# bare-bones-arduino.net
KiCad netlist of a schematic drawn in EAGLE
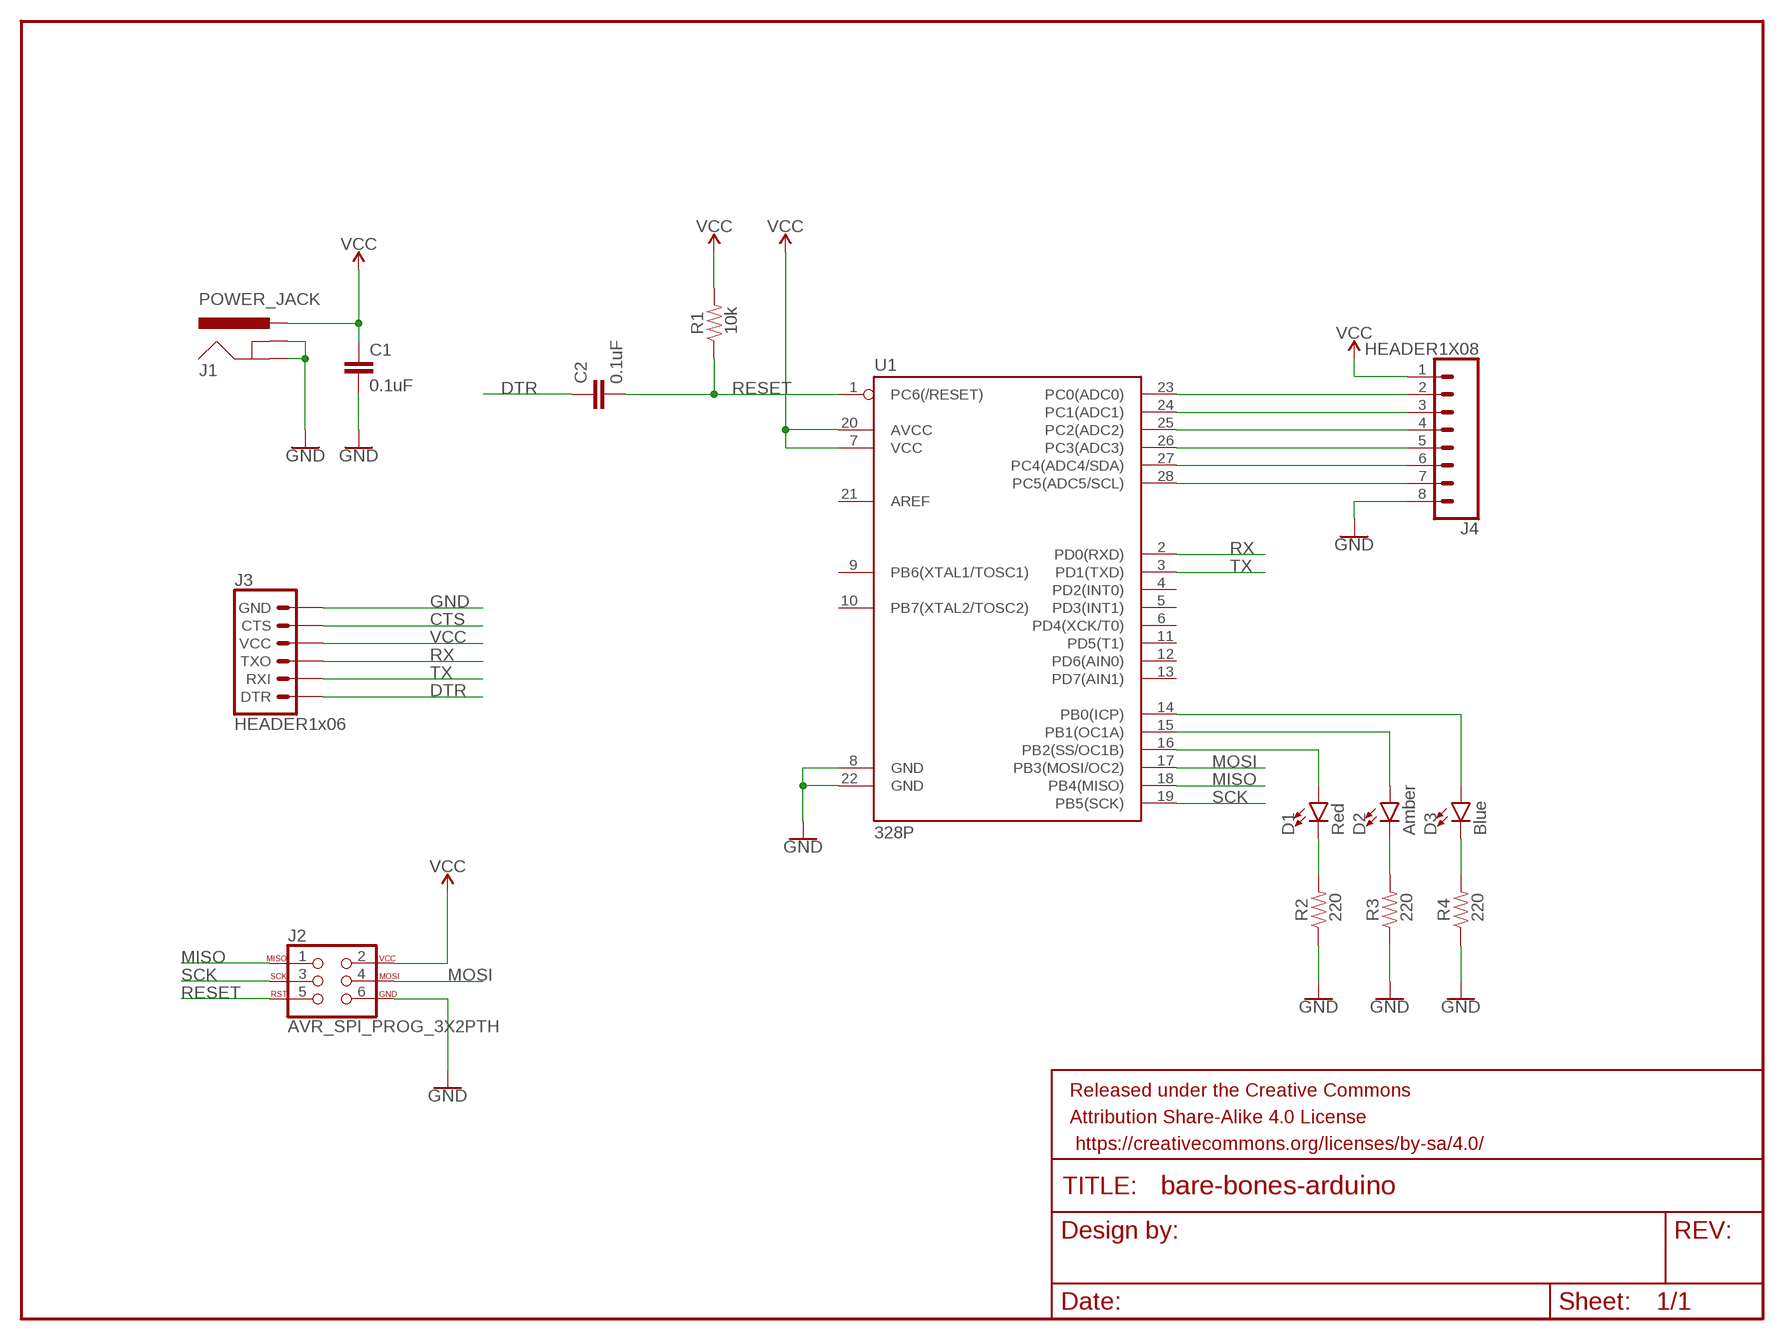
[diagram p0: schematic, sheet 1]

(export (version "E")
  (design (tool "Eeschema 10.0.6"))
  (components
    (comp (ref "C1")
      (value "0.1uF")
      (footprint "eagle-import:CAP-PTH-SMALL-KIT")
      (libsource (lib "eagle-import") (part "0.1UF-KIT-EZ-50V-20%"))
    )
    (comp (ref "C2")
      (value "0.1uF")
      (footprint "eagle-import:CAP-PTH-SMALL-KIT")
      (libsource (lib "eagle-import") (part "0.1UF-KIT-EZ-50V-20%"))
    )
    (comp (ref "D1")
      (value "Red")
      (footprint "eagle-import:LED_5MM")
      (libsource (lib "eagle-import") (part "LED5MM"))
    )
    (comp (ref "D2")
      (value "Amber")
      (footprint "eagle-import:LED_5MM")
      (libsource (lib "eagle-import") (part "LED5MM"))
    )
    (comp (ref "D3")
      (value "Blue")
      (footprint "eagle-import:LED_5MM")
      (libsource (lib "eagle-import") (part "LED5MM"))
    )
    (comp (ref "FRAME1")
      (value "FRAME-LETTERNO_PACKAGE")
      (footprint "eagle-import:DUMMY")
      (fields (field (name "DESIGNER") "Nobody"))
      (libsource (lib "eagle-import") (part "FRAME-LETTERNO_PACKAGE"))
    )
    (comp (ref "J1")
      (value "POWER_JACK")
      (footprint "eagle-import:POWER_JACK_PTH")
      (libsource (lib "eagle-import") (part "POWER_JACK"))
    )
    (comp (ref "J2")
      (value "AVR_SPI_PROG_3X2PTH")
      (footprint "eagle-import:2X3")
      (libsource (lib "eagle-import") (part "AVR_SPI_PROG_3X2PTH"))
    )
    (comp (ref "J3")
      (value "HEADER1x06")
      (footprint "eagle-import:1X06")
      (libsource (lib "eagle-import") (part "6_PIN_SERIAL_TARGET"))
    )
    (comp (ref "J4")
      (value "HEADER1X08")
      (footprint "eagle-import:1X08")
      (libsource (lib "eagle-import") (part "CONN_08{dblquote}"))
    )
    (comp (ref "R1")
      (value "10k")
      (footprint "eagle-import:AXIAL-0.3")
      (libsource (lib "eagle-import") (part "RESISTORAXIAL-0.3"))
    )
    (comp (ref "R2")
      (value "220")
      (footprint "eagle-import:AXIAL-0.3")
      (libsource (lib "eagle-import") (part "RESISTORAXIAL-0.3"))
    )
    (comp (ref "R3")
      (value "220")
      (footprint "eagle-import:AXIAL-0.3")
      (libsource (lib "eagle-import") (part "RESISTORAXIAL-0.3"))
    )
    (comp (ref "R4")
      (value "220")
      (footprint "eagle-import:AXIAL-0.3")
      (libsource (lib "eagle-import") (part "RESISTORAXIAL-0.3"))
    )
    (comp (ref "U1")
      (value "328P")
      (footprint "eagle-import:DIP28")
      (libsource (lib "eagle-import") (part "ATMEGA328P_PDIP"))
    )
  )
  (nets
    (net (code "1") (name "/CTS") (class "Default")
      (node (ref "J3") (pin "5") (pinfunction "CTS_5") (pintype "passive"))
    )
    (net (code "2") (name "/DTR") (class "Default")
      (node (ref "C2") (pin "1") (pinfunction "1_1") (pintype "passive"))
      (node (ref "J3") (pin "1") (pinfunction "DTR_1") (pintype "passive"))
    )
    (net (code "3") (name "/MISO") (class "Default")
      (node (ref "J2") (pin "1") (pinfunction "1_1") (pintype "passive"))
      (node (ref "U1") (pin "18") (pinfunction "PB4(MISO)_18") (pintype "bidirectional"))
    )
    (net (code "4") (name "/MOSI") (class "Default")
      (node (ref "J2") (pin "4") (pinfunction "4_4") (pintype "passive"))
      (node (ref "U1") (pin "17") (pinfunction "PB3(MOSI/OC2)_17") (pintype "bidirectional"))
    )
    (net (code "5") (name "/RESET") (class "Default")
      (node (ref "C2") (pin "2") (pinfunction "2_2") (pintype "passive"))
      (node (ref "J2") (pin "5") (pinfunction "5_5") (pintype "passive"))
      (node (ref "R1") (pin "P$1") (pinfunction "1_P$1") (pintype "passive"))
      (node (ref "U1") (pin "1") (pinfunction "PC6(/RESET)_1") (pintype "bidirectional"))
    )
    (net (code "6") (name "/RX") (class "Default")
      (node (ref "J3") (pin "3") (pinfunction "TXO_3") (pintype "passive"))
      (node (ref "U1") (pin "2") (pinfunction "PD0(RXD)_2") (pintype "bidirectional"))
    )
    (net (code "7") (name "/SCK") (class "Default")
      (node (ref "J2") (pin "3") (pinfunction "3_3") (pintype "passive"))
      (node (ref "U1") (pin "19") (pinfunction "PB5(SCK)_19") (pintype "bidirectional"))
    )
    (net (code "8") (name "/TX") (class "Default")
      (node (ref "J3") (pin "2") (pinfunction "RXI_2") (pintype "passive"))
      (node (ref "U1") (pin "3") (pinfunction "PD1(TXD)_3") (pintype "bidirectional"))
    )
    (net (code "9") (name "GND") (class "Default")
      (node (ref "C1") (pin "2") (pinfunction "2_2") (pintype "passive"))
      (node (ref "J1") (pin "GND") (pinfunction "GND_GND") (pintype "bidirectional"))
      (node (ref "J1") (pin "GNDBREAK") (pinfunction "GNDBREAK_GNDBREAK") (pintype "bidirectional"))
      (node (ref "J2") (pin "6") (pinfunction "6_6") (pintype "passive"))
      (node (ref "J3") (pin "6") (pinfunction "GND_6") (pintype "passive"))
      (node (ref "J4") (pin "8") (pinfunction "8_8") (pintype "passive"))
      (node (ref "R2") (pin "P$1") (pinfunction "1_P$1") (pintype "passive"))
      (node (ref "R3") (pin "P$1") (pinfunction "1_P$1") (pintype "passive"))
      (node (ref "R4") (pin "P$1") (pinfunction "1_P$1") (pintype "passive"))
      (node (ref "U1") (pin "22") (pinfunction "GND_22") (pintype "bidirectional"))
      (node (ref "U1") (pin "8") (pinfunction "GND_8") (pintype "bidirectional"))
    )
    (net (code "10") (name "Net-(D1-C)") (class "Default")
      (node (ref "D1") (pin "K") (pinfunction "C_K") (pintype "passive"))
      (node (ref "R2") (pin "P$2") (pinfunction "2_P$2") (pintype "passive"))
    )
    (net (code "11") (name "Net-(D2-C)") (class "Default")
      (node (ref "D2") (pin "K") (pinfunction "C_K") (pintype "passive"))
      (node (ref "R3") (pin "P$2") (pinfunction "2_P$2") (pintype "passive"))
    )
    (net (code "12") (name "Net-(D3-C)") (class "Default")
      (node (ref "D3") (pin "K") (pinfunction "C_K") (pintype "passive"))
      (node (ref "R4") (pin "P$2") (pinfunction "2_P$2") (pintype "passive"))
    )
    (net (code "13") (name "Net-(U1-PB0(ICP))") (class "Default")
      (node (ref "D3") (pin "A") (pinfunction "A_A") (pintype "passive"))
      (node (ref "U1") (pin "14") (pinfunction "PB0(ICP)_14") (pintype "bidirectional"))
    )
    (net (code "14") (name "Net-(U1-PB1(OC1A))") (class "Default")
      (node (ref "D2") (pin "A") (pinfunction "A_A") (pintype "passive"))
      (node (ref "U1") (pin "15") (pinfunction "PB1(OC1A)_15") (pintype "bidirectional"))
    )
    (net (code "15") (name "Net-(U1-PB2(SS{slash}OC1B))") (class "Default")
      (node (ref "D1") (pin "A") (pinfunction "A_A") (pintype "passive"))
      (node (ref "U1") (pin "16") (pinfunction "PB2(SS/OC1B)_16") (pintype "bidirectional"))
    )
    (net (code "16") (name "Net-(U1-PC0(ADC0))") (class "Default")
      (node (ref "J4") (pin "2") (pinfunction "2_2") (pintype "passive"))
      (node (ref "U1") (pin "23") (pinfunction "PC0(ADC0)_23") (pintype "bidirectional"))
    )
    (net (code "17") (name "Net-(U1-PC1(ADC1))") (class "Default")
      (node (ref "J4") (pin "3") (pinfunction "3_3") (pintype "passive"))
      (node (ref "U1") (pin "24") (pinfunction "PC1(ADC1)_24") (pintype "bidirectional"))
    )
    (net (code "18") (name "Net-(U1-PC2(ADC2))") (class "Default")
      (node (ref "J4") (pin "4") (pinfunction "4_4") (pintype "passive"))
      (node (ref "U1") (pin "25") (pinfunction "PC2(ADC2)_25") (pintype "bidirectional"))
    )
    (net (code "19") (name "Net-(U1-PC3(ADC3))") (class "Default")
      (node (ref "J4") (pin "5") (pinfunction "5_5") (pintype "passive"))
      (node (ref "U1") (pin "26") (pinfunction "PC3(ADC3)_26") (pintype "bidirectional"))
    )
    (net (code "20") (name "Net-(U1-PC4(ADC4{slash}SDA))") (class "Default")
      (node (ref "J4") (pin "6") (pinfunction "6_6") (pintype "passive"))
      (node (ref "U1") (pin "27") (pinfunction "PC4(ADC4/SDA)_27") (pintype "bidirectional"))
    )
    (net (code "21") (name "Net-(U1-PC5(ADC5{slash}SCL))") (class "Default")
      (node (ref "J4") (pin "7") (pinfunction "7_7") (pintype "passive"))
      (node (ref "U1") (pin "28") (pinfunction "PC5(ADC5/SCL)_28") (pintype "bidirectional"))
    )
    (net (code "22") (name "VCC") (class "Default")
      (node (ref "C1") (pin "1") (pinfunction "1_1") (pintype "passive"))
      (node (ref "J1") (pin "PWR") (pinfunction "PWR_PWR") (pintype "bidirectional"))
      (node (ref "J2") (pin "2") (pinfunction "2_2") (pintype "passive"))
      (node (ref "J3") (pin "4") (pinfunction "VCC_4") (pintype "passive"))
      (node (ref "J4") (pin "1") (pinfunction "1_1") (pintype "passive"))
      (node (ref "R1") (pin "P$2") (pinfunction "2_P$2") (pintype "passive"))
      (node (ref "U1") (pin "20") (pinfunction "AVCC_20") (pintype "bidirectional"))
      (node (ref "U1") (pin "7") (pinfunction "VCC_7") (pintype "bidirectional"))
    )
    (net (code "23") (name "unconnected-(U1-AREF-Pad21)") (class "Default")
      (node (ref "U1") (pin "21") (pinfunction "AREF_21") (pintype "bidirectional"))
    )
    (net (code "24") (name "unconnected-(U1-PB6(XTAL1{slash}TOSC1)-Pad9)") (class "Default")
      (node (ref "U1") (pin "9") (pinfunction "PB6(XTAL1/TOSC1)_9") (pintype "bidirectional"))
    )
    (net (code "25") (name "unconnected-(U1-PB7(XTAL2{slash}TOSC2)-Pad10)") (class "Default")
      (node (ref "U1") (pin "10") (pinfunction "PB7(XTAL2/TOSC2)_10") (pintype "bidirectional"))
    )
    (net (code "26") (name "unconnected-(U1-PD2(INT0)-Pad4)") (class "Default")
      (node (ref "U1") (pin "4") (pinfunction "PD2(INT0)_4") (pintype "bidirectional"))
    )
    (net (code "27") (name "unconnected-(U1-PD3(INT1)-Pad5)") (class "Default")
      (node (ref "U1") (pin "5") (pinfunction "PD3(INT1)_5") (pintype "bidirectional"))
    )
    (net (code "28") (name "unconnected-(U1-PD4(XCK{slash}T0)-Pad6)") (class "Default")
      (node (ref "U1") (pin "6") (pinfunction "PD4(XCK/T0)_6") (pintype "bidirectional"))
    )
    (net (code "29") (name "unconnected-(U1-PD5(T1)-Pad11)") (class "Default")
      (node (ref "U1") (pin "11") (pinfunction "PD5(T1)_11") (pintype "bidirectional"))
    )
    (net (code "30") (name "unconnected-(U1-PD6(AIN0)-Pad12)") (class "Default")
      (node (ref "U1") (pin "12") (pinfunction "PD6(AIN0)_12") (pintype "bidirectional"))
    )
    (net (code "31") (name "unconnected-(U1-PD7(AIN1)-Pad13)") (class "Default")
      (node (ref "U1") (pin "13") (pinfunction "PD7(AIN1)_13") (pintype "bidirectional"))
    )
  )
)
